# 12V_LS.net
KiCad netlist of a schematic drawn in Altium Designer
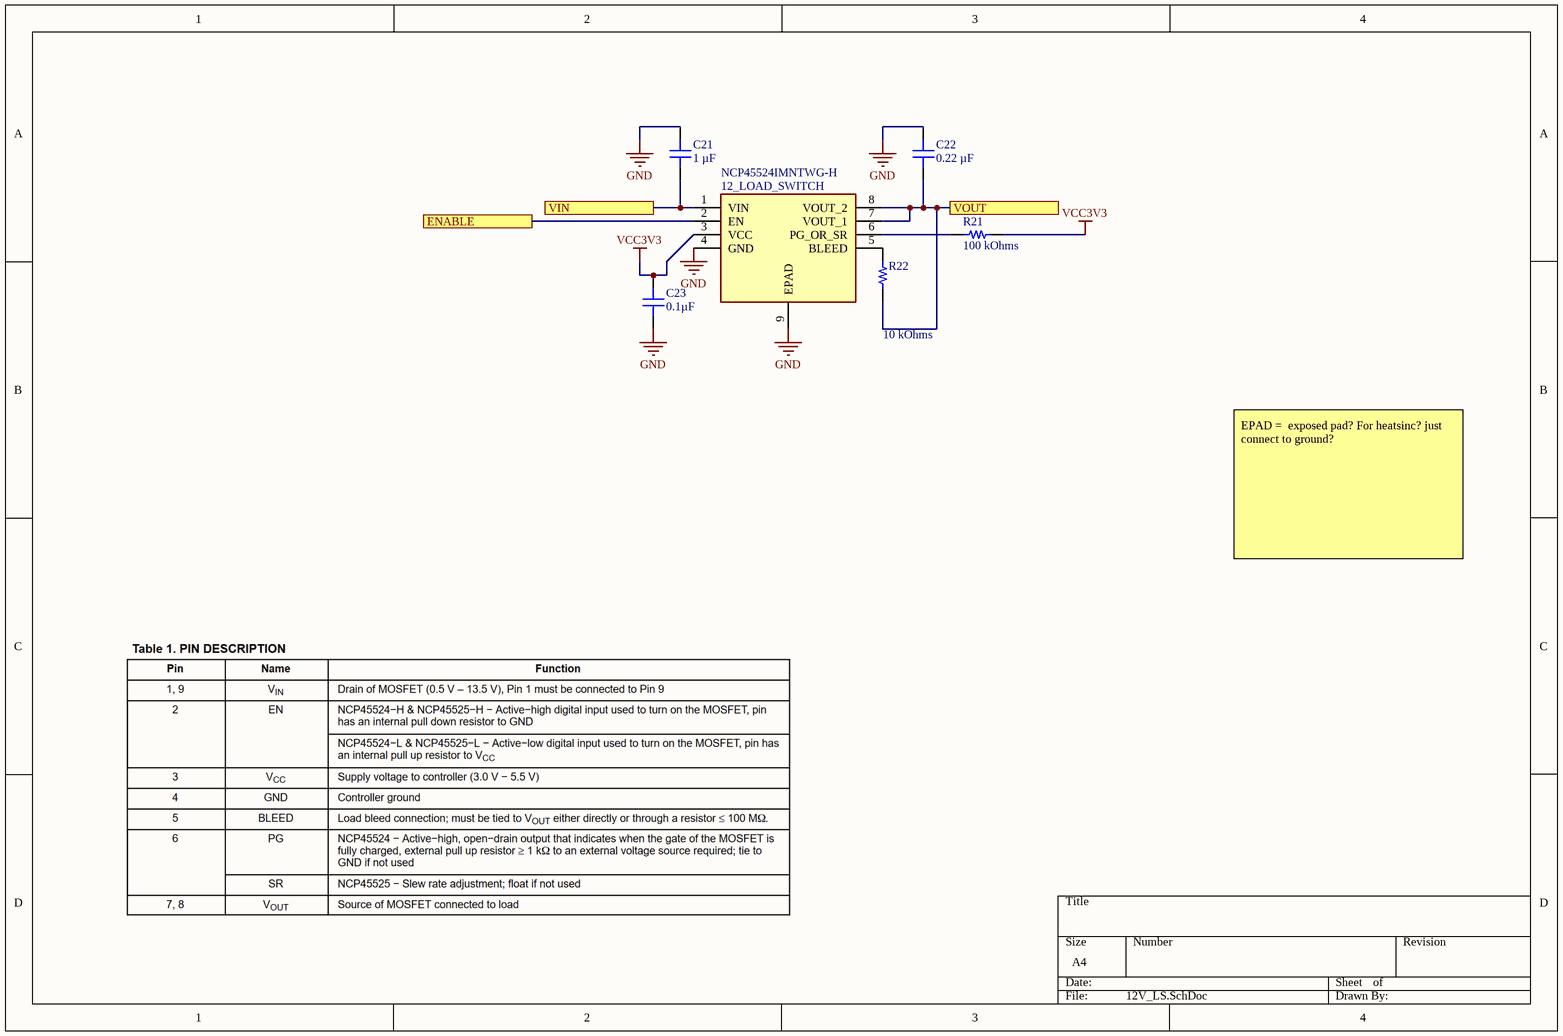
[diagram p0: 12V_LS.SchDoc]

(export (version "E")
  (design (tool "Eeschema 10.0.6"))
  (components
    (comp (ref "12_LOAD_SWITCH")
      (value "NCP45524IMNTWG-H")
      (footprint "SON50P200X200X100-9N")
      (description "Integrated Circuit")
      (fields (field (name "MOUSER PART NUMBER") "863-NCP45524IMNTWG-H"))
      (libsource (lib "NCP45524IMNTWG-H") (part "NCP45524IMNTWG-H"))
    )
    (comp (ref "C21")
      (value "1 µF")
      (footprint "CAP 0402_1005")
      (description "CAP CER 1UF 10V X7S 0402")
      (fields
        (field (name "PART NUMBER") "GRM155C71A105KE11D")
        (field (name "MANUFACTURER") "Murata Electronics")
      )
      (libsource (lib "Celestial") (part "Capacitor"))
    )
    (comp (ref "C22")
      (value "0.22 µF")
      (footprint "CAP 0603_1608")
      (description "CAP CER 0.22UF 25V X7R 0603")
      (fields (field (name "PART NUMBER") "CC0603KRX7R8BB224") (field (name "MANUFACTURER") "Yageo"))
      (libsource (lib "Celestial Altium Library - altium_library") (part "Capacitor"))
    )
    (comp (ref "C23")
      (value "0.1µF")
      (footprint "CAP 0402_1005")
      (description "CAP CER 0.1UF 10V X7R 0402")
      (fields (field (name "PART NUMBER") "0402ZC104KAT2A") (field (name "MANUFACTURER") "AVX Corporation"))
      (libsource (lib "Celestial") (part "Capacitor"))
    )
    (comp (ref "R21")
      (value "100 kOhms")
      (footprint "RES 0603_1608")
      (description "RES 100K OHM 0.1% 1/16W 0603")
      (fields
        (field (name "PART NUMBER") "RNCS0603BKE100K")
        (field (name "MANUFACTURER") "Stackpole Electronics Inc")
      )
      (libsource (lib "Celestial Altium Library - altium_library") (part "Resistor"))
    )
    (comp (ref "R22")
      (value "10 kOhms")
      (footprint "RES 0603_1608")
      (description "RES 10K OHM 0.1% 1/16W 0603")
      (fields
        (field (name "PART NUMBER") "RNCS0603BKE10K0")
        (field (name "MANUFACTURER") "Stackpole Electronics Inc")
      )
      (libsource (lib "Celestial Altium Library - altium_library") (part "Resistor"))
    )
  )
  (nets
    (net (code "1") (name "/ENABLE") (class "Default")
      (node (ref "12_LOAD_SWITCH") (pin "2") (pinfunction "EN_2") (pintype "passive"))
    )
    (net (code "2") (name "/VIN") (class "Default")
      (node (ref "12_LOAD_SWITCH") (pin "1") (pinfunction "VIN_1") (pintype "passive"))
      (node (ref "C21") (pin "1") (pinfunction "1_1") (pintype "passive"))
    )
    (net (code "3") (name "/VOUT") (class "Default")
      (node (ref "12_LOAD_SWITCH") (pin "7") (pinfunction "VOUT_1_7") (pintype "passive"))
      (node (ref "12_LOAD_SWITCH") (pin "8") (pinfunction "VOUT_2_8") (pintype "passive"))
      (node (ref "C22") (pin "1") (pinfunction "1_1") (pintype "passive"))
      (node (ref "R22") (pin "1") (pinfunction "1_1") (pintype "passive"))
    )
    (net (code "4") (name "GND") (class "Default")
      (node (ref "12_LOAD_SWITCH") (pin "4") (pinfunction "GND_4") (pintype "passive"))
      (node (ref "12_LOAD_SWITCH") (pin "9") (pinfunction "EPAD_9") (pintype "passive"))
      (node (ref "C21") (pin "2") (pinfunction "2_2") (pintype "passive"))
      (node (ref "C22") (pin "2") (pinfunction "2_2") (pintype "passive"))
      (node (ref "C23") (pin "1") (pinfunction "1_1") (pintype "passive"))
    )
    (net (code "5") (name "Net-(12_LOAD_SWITCH-BLEED)") (class "Default")
      (node (ref "12_LOAD_SWITCH") (pin "5") (pinfunction "BLEED_5") (pintype "passive"))
      (node (ref "R22") (pin "2") (pinfunction "2_2") (pintype "passive"))
    )
    (net (code "6") (name "Net-(12_LOAD_SWITCH-PG_OR_SR)") (class "Default")
      (node (ref "12_LOAD_SWITCH") (pin "6") (pinfunction "PG_OR_SR_6") (pintype "passive"))
      (node (ref "R21") (pin "1") (pinfunction "1_1") (pintype "passive"))
    )
    (net (code "7") (name "VCC3V3") (class "Default")
      (node (ref "12_LOAD_SWITCH") (pin "3") (pinfunction "VCC_3") (pintype "passive"))
      (node (ref "C23") (pin "2") (pinfunction "2_2") (pintype "passive"))
      (node (ref "R21") (pin "2") (pinfunction "2_2") (pintype "passive"))
    )
  )
)
